# Microcontroller.net
KiCad netlist of a schematic drawn in Altium Designer
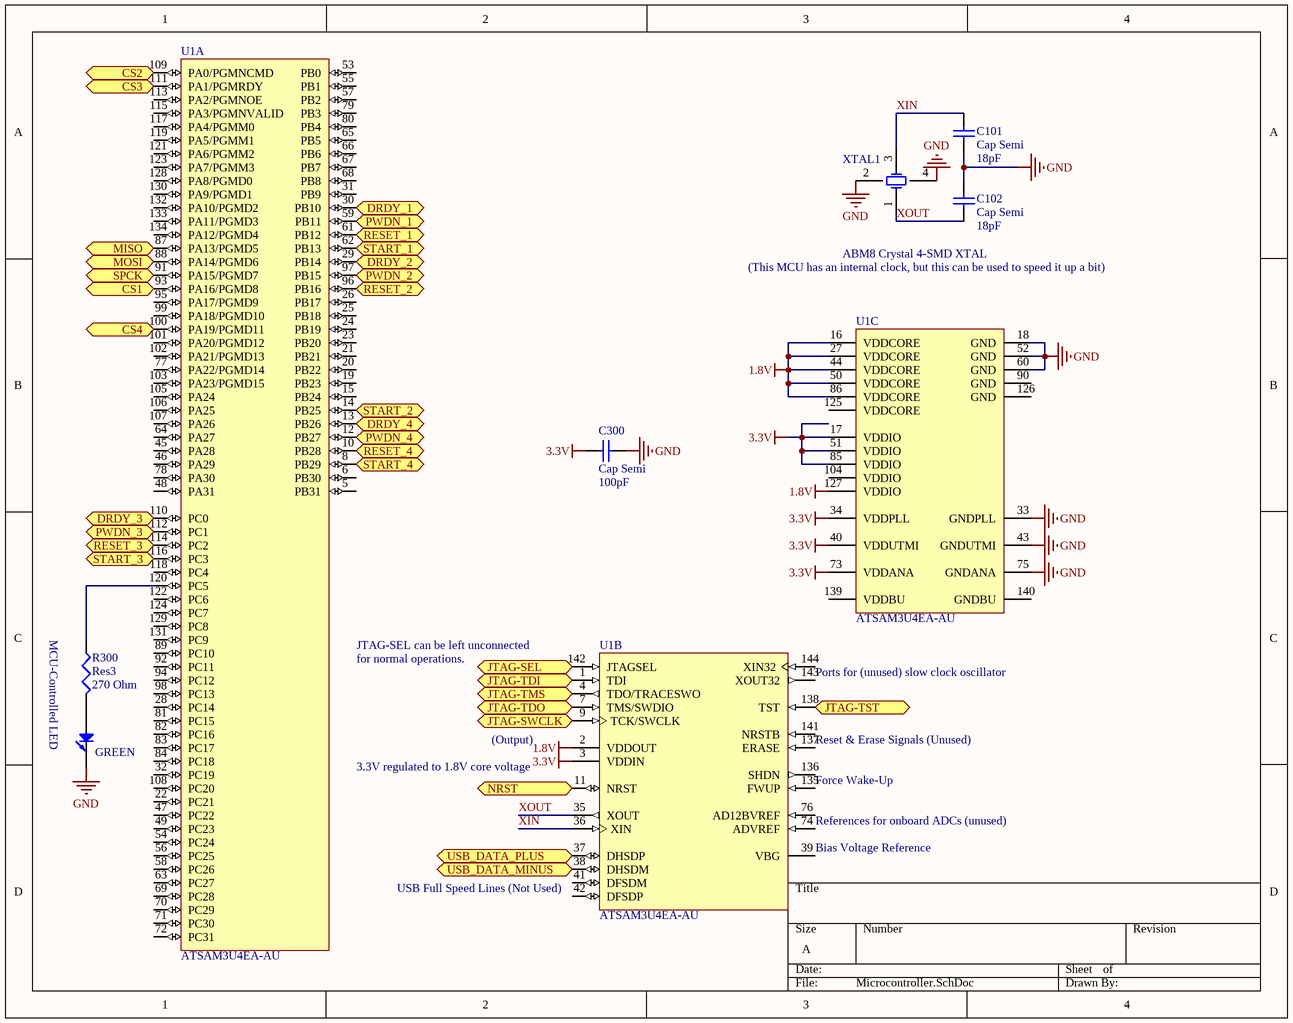
[diagram p0: Microcontroller.SchDoc]

(export (version "E")
  (design (tool "Eeschema 10.0.6"))
  (components
    (comp (ref "C101")
      (value "Cap Semi")
      (footprint "1608[0603]")
      (description "Capacitor (Semiconductor SIM Model)")
      (fields (field (name "ALTIUM_VALUE") "18pF") (field (name "PUBLISHER") "Altium Limited"))
      (libsource (lib "Miscellaneous Devices") (part "Cap Semi"))
    )
    (comp (ref "C102")
      (value "Cap Semi")
      (footprint "1608[0603]")
      (description "Capacitor (Semiconductor SIM Model)")
      (fields (field (name "ALTIUM_VALUE") "18pF") (field (name "PUBLISHER") "Altium Limited"))
      (libsource (lib "Miscellaneous Devices") (part "Cap Semi"))
    )
    (comp (ref "C300")
      (value "Cap Semi")
      (footprint "C1206")
      (description "Capacitor (Semiconductor SIM Model)")
      (fields (field (name "ALTIUM_VALUE") "100pF") (field (name "PUBLISHER") "Altium Limited"))
      (libsource (lib "Miscellaneous Devices") (part "Cap Semi"))
    )
    (comp (ref "LED2")
      (value "GREEN")
      (footprint "1608[0603]")
      (description "led")
      (fields
        (field (name "MANUFACTURER") "Lite-On Inc")
        (field (name "MANUFACTURER PART NUMBER") "LTST-C193KGKT-5A")
      )
      (libsource (lib "common") (part "LED0"))
    )
    (comp (ref "R300")
      (value "Res3")
      (footprint "1608[0603]")
      (description "Resistor")
      (fields (field (name "ALTIUM_VALUE") "270 Ohm") (field (name "PUBLISHER") "Altium Limited"))
      (libsource (lib "Miscellaneous Devices") (part "Res3"))
    )
    (comp (ref "U1")
      (value "ATSAM3U4EA-AU")
      (footprint "144L1_N")
      (fields (field (name "PUBLISHER") "Altium Limited"))
      (libsource (lib "Atmel Microcontroller 32-Bit ARM") (part "ATSAM3U4EA-AU"))
    )
    (comp (ref "XTAL1")
      (value "ABM8 Crystal 4-SMD XTAL")
      (footprint "ABM8 Crystal XTAL")
      (description "SMD Crystal")
      (libsource (lib "common") (part "ABM8 Crystal 4-SMD XTAL_1"))
    )
  )
  (nets
    (net (code "1") (name "/CS1") (class "Default")
      (node (ref "U1") (pin "93") (pinfunction "PA16/PGMD8_93") (pintype "bidirectional"))
    )
    (net (code "2") (name "/CS2") (class "Default")
      (node (ref "U1") (pin "109") (pinfunction "PA0/PGMNCMD_109") (pintype "bidirectional"))
    )
    (net (code "3") (name "/CS3") (class "Default")
      (node (ref "U1") (pin "111") (pinfunction "PA1/PGMRDY_111") (pintype "bidirectional"))
    )
    (net (code "4") (name "/CS4") (class "Default")
      (node (ref "U1") (pin "100") (pinfunction "PA19/PGMD11_100") (pintype "bidirectional"))
    )
    (net (code "5") (name "/DRDY_1") (class "Default")
      (node (ref "U1") (pin "30") (pinfunction "PB10_30") (pintype "bidirectional"))
    )
    (net (code "6") (name "/DRDY_2") (class "Default")
      (node (ref "U1") (pin "29") (pinfunction "PB14_29") (pintype "bidirectional"))
    )
    (net (code "7") (name "/DRDY_3") (class "Default")
      (node (ref "U1") (pin "110") (pinfunction "PC0_110") (pintype "bidirectional"))
    )
    (net (code "8") (name "/DRDY_4") (class "Default")
      (node (ref "U1") (pin "13") (pinfunction "PB26_13") (pintype "bidirectional"))
    )
    (net (code "9") (name "/JTAG-SEL") (class "Default")
      (node (ref "U1") (pin "142") (pinfunction "JTAGSEL_142") (pintype "input"))
    )
    (net (code "10") (name "/JTAG-SWCLK") (class "Default")
      (node (ref "U1") (pin "9") (pinfunction "TCK/SWCLK_9") (pintype "input"))
    )
    (net (code "11") (name "/JTAG-TDI") (class "Default")
      (node (ref "U1") (pin "1") (pinfunction "TDI_1") (pintype "input"))
    )
    (net (code "12") (name "/JTAG-TDO") (class "Default")
      (node (ref "U1") (pin "7") (pinfunction "TMS/SWDIO_7") (pintype "input"))
    )
    (net (code "13") (name "/JTAG-TMS") (class "Default")
      (node (ref "U1") (pin "4") (pinfunction "TDO/TRACESWO_4") (pintype "output"))
    )
    (net (code "14") (name "/JTAG-TST") (class "Default")
      (node (ref "U1") (pin "138") (pinfunction "TST_138") (pintype "input"))
    )
    (net (code "15") (name "/MISO") (class "Default")
      (node (ref "U1") (pin "87") (pinfunction "PA13/PGMD5_87") (pintype "bidirectional"))
    )
    (net (code "16") (name "/MOSI") (class "Default")
      (node (ref "U1") (pin "88") (pinfunction "PA14/PGMD6_88") (pintype "bidirectional"))
    )
    (net (code "17") (name "/NRST") (class "Default")
      (node (ref "U1") (pin "11") (pinfunction "NRST_11") (pintype "bidirectional"))
    )
    (net (code "18") (name "/PWDN_1") (class "Default")
      (node (ref "U1") (pin "59") (pinfunction "PB11_59") (pintype "bidirectional"))
    )
    (net (code "19") (name "/PWDN_2") (class "Default")
      (node (ref "U1") (pin "97") (pinfunction "PB15_97") (pintype "bidirectional"))
    )
    (net (code "20") (name "/PWDN_3") (class "Default")
      (node (ref "U1") (pin "112") (pinfunction "PC1_112") (pintype "bidirectional"))
    )
    (net (code "21") (name "/PWDN_4") (class "Default")
      (node (ref "U1") (pin "12") (pinfunction "PB27_12") (pintype "bidirectional"))
    )
    (net (code "22") (name "/RESET_1") (class "Default")
      (node (ref "U1") (pin "61") (pinfunction "PB12_61") (pintype "bidirectional"))
    )
    (net (code "23") (name "/RESET_2") (class "Default")
      (node (ref "U1") (pin "96") (pinfunction "PB16_96") (pintype "bidirectional"))
    )
    (net (code "24") (name "/RESET_3") (class "Default")
      (node (ref "U1") (pin "114") (pinfunction "PC2_114") (pintype "bidirectional"))
    )
    (net (code "25") (name "/RESET_4") (class "Default")
      (node (ref "U1") (pin "10") (pinfunction "PB28_10") (pintype "bidirectional"))
    )
    (net (code "26") (name "/SPCK") (class "Default")
      (node (ref "U1") (pin "91") (pinfunction "PA15/PGMD7_91") (pintype "bidirectional"))
    )
    (net (code "27") (name "/START_1") (class "Default")
      (node (ref "U1") (pin "62") (pinfunction "PB13_62") (pintype "bidirectional"))
    )
    (net (code "28") (name "/START_2") (class "Default")
      (node (ref "U1") (pin "14") (pinfunction "PB25_14") (pintype "bidirectional"))
    )
    (net (code "29") (name "/START_3") (class "Default")
      (node (ref "U1") (pin "116") (pinfunction "PC3_116") (pintype "bidirectional"))
    )
    (net (code "30") (name "/START_4") (class "Default")
      (node (ref "U1") (pin "8") (pinfunction "PB29_8") (pintype "bidirectional"))
    )
    (net (code "31") (name "/USB_DATA_MINUS") (class "Default")
      (node (ref "U1") (pin "38") (pinfunction "DHSDM_38") (pintype "bidirectional"))
    )
    (net (code "32") (name "/USB_DATA_PLUS") (class "Default")
      (node (ref "U1") (pin "37") (pinfunction "DHSDP_37") (pintype "bidirectional"))
    )
    (net (code "33") (name "/XIN") (class "Default")
      (node (ref "C101") (pin "2") (pinfunction "2_2") (pintype "passive"))
      (node (ref "U1") (pin "36") (pinfunction "XIN_36") (pintype "input"))
      (node (ref "XTAL1") (pin "3") (pinfunction "OSC2_3") (pintype "passive"))
    )
    (net (code "34") (name "/XOUT") (class "Default")
      (node (ref "C102") (pin "1") (pinfunction "1_1") (pintype "passive"))
      (node (ref "U1") (pin "35") (pinfunction "XOUT_35") (pintype "output"))
      (node (ref "XTAL1") (pin "1") (pinfunction "OSC1_1") (pintype "passive"))
    )
    (net (code "35") (name "1.8V") (class "Default")
      (node (ref "U1") (pin "127") (pinfunction "VDDIO_127") (pintype "power_in"))
      (node (ref "U1") (pin "16") (pinfunction "VDDCORE_16") (pintype "power_in"))
      (node (ref "U1") (pin "2") (pinfunction "VDDOUT_2") (pintype "power_in"))
      (node (ref "U1") (pin "27") (pinfunction "VDDCORE_27") (pintype "power_in"))
      (node (ref "U1") (pin "44") (pinfunction "VDDCORE_44") (pintype "power_in"))
      (node (ref "U1") (pin "50") (pinfunction "VDDCORE_50") (pintype "power_in"))
      (node (ref "U1") (pin "86") (pinfunction "VDDCORE_86") (pintype "power_in"))
    )
    (net (code "36") (name "3.3V") (class "Default")
      (node (ref "C300") (pin "1") (pinfunction "1_1") (pintype "passive"))
      (node (ref "U1") (pin "17") (pinfunction "VDDIO_17") (pintype "power_in"))
      (node (ref "U1") (pin "3") (pinfunction "VDDIN_3") (pintype "power_in"))
      (node (ref "U1") (pin "34") (pinfunction "VDDPLL_34") (pintype "power_in"))
      (node (ref "U1") (pin "40") (pinfunction "VDDUTMI_40") (pintype "power_in"))
      (node (ref "U1") (pin "51") (pinfunction "VDDIO_51") (pintype "power_in"))
      (node (ref "U1") (pin "73") (pinfunction "VDDANA_73") (pintype "power_in"))
      (node (ref "U1") (pin "85") (pinfunction "VDDIO_85") (pintype "power_in"))
    )
    (net (code "37") (name "GND") (class "Default")
      (node (ref "C101") (pin "1") (pinfunction "1_1") (pintype "passive"))
      (node (ref "C102") (pin "2") (pinfunction "2_2") (pintype "passive"))
      (node (ref "C300") (pin "2") (pinfunction "2_2") (pintype "passive"))
      (node (ref "LED2") (pin "2") (pinfunction "K_2") (pintype "passive"))
      (node (ref "U1") (pin "18") (pinfunction "GND_18") (pintype "power_in"))
      (node (ref "U1") (pin "33") (pinfunction "GNDPLL_33") (pintype "power_in"))
      (node (ref "U1") (pin "43") (pinfunction "GNDUTMI_43") (pintype "power_in"))
      (node (ref "U1") (pin "52") (pinfunction "GND_52") (pintype "power_in"))
      (node (ref "U1") (pin "60") (pinfunction "GND_60") (pintype "power_in"))
      (node (ref "U1") (pin "75") (pinfunction "GNDANA_75") (pintype "power_in"))
      (node (ref "XTAL1") (pin "2") (pinfunction "GND_2") (pintype "passive"))
      (node (ref "XTAL1") (pin "4") (pinfunction "GND_4") (pintype "power_in"))
    )
    (net (code "38") (name "Net-(LED2-A)") (class "Default")
      (node (ref "LED2") (pin "1") (pinfunction "A_1") (pintype "passive"))
      (node (ref "R300") (pin "2") (pinfunction "2_2") (pintype "passive"))
    )
    (net (code "39") (name "Net-(U1A-PC5)") (class "Default")
      (node (ref "R300") (pin "1") (pinfunction "1_1") (pintype "passive"))
      (node (ref "U1") (pin "120") (pinfunction "PC5_120") (pintype "bidirectional"))
    )
    (net (code "40") (name "unconnected-(U1A-PA2{slash}PGMNOE-Pad113)") (class "Default")
      (node (ref "U1") (pin "113") (pinfunction "PA2/PGMNOE_113") (pintype "bidirectional"))
    )
    (net (code "41") (name "unconnected-(U1A-PA3{slash}PGMNVALID-Pad115)") (class "Default")
      (node (ref "U1") (pin "115") (pinfunction "PA3/PGMNVALID_115") (pintype "bidirectional"))
    )
    (net (code "42") (name "unconnected-(U1A-PA4{slash}PGMM0-Pad117)") (class "Default")
      (node (ref "U1") (pin "117") (pinfunction "PA4/PGMM0_117") (pintype "bidirectional"))
    )
    (net (code "43") (name "unconnected-(U1A-PA5{slash}PGMM1-Pad119)") (class "Default")
      (node (ref "U1") (pin "119") (pinfunction "PA5/PGMM1_119") (pintype "bidirectional"))
    )
    (net (code "44") (name "unconnected-(U1A-PA6{slash}PGMM2-Pad121)") (class "Default")
      (node (ref "U1") (pin "121") (pinfunction "PA6/PGMM2_121") (pintype "bidirectional"))
    )
    (net (code "45") (name "unconnected-(U1A-PA7{slash}PGMM3-Pad123)") (class "Default")
      (node (ref "U1") (pin "123") (pinfunction "PA7/PGMM3_123") (pintype "bidirectional"))
    )
    (net (code "46") (name "unconnected-(U1A-PA8{slash}PGMD0-Pad128)") (class "Default")
      (node (ref "U1") (pin "128") (pinfunction "PA8/PGMD0_128") (pintype "bidirectional"))
    )
    (net (code "47") (name "unconnected-(U1A-PA9{slash}PGMD1-Pad130)") (class "Default")
      (node (ref "U1") (pin "130") (pinfunction "PA9/PGMD1_130") (pintype "bidirectional"))
    )
    (net (code "48") (name "unconnected-(U1A-PA10{slash}PGMD2-Pad132)") (class "Default")
      (node (ref "U1") (pin "132") (pinfunction "PA10/PGMD2_132") (pintype "bidirectional"))
    )
    (net (code "49") (name "unconnected-(U1A-PA11{slash}PGMD3-Pad133)") (class "Default")
      (node (ref "U1") (pin "133") (pinfunction "PA11/PGMD3_133") (pintype "bidirectional"))
    )
    (net (code "50") (name "unconnected-(U1A-PA12{slash}PGMD4-Pad134)") (class "Default")
      (node (ref "U1") (pin "134") (pinfunction "PA12/PGMD4_134") (pintype "bidirectional"))
    )
    (net (code "51") (name "unconnected-(U1A-PA17{slash}PGMD9-Pad95)") (class "Default")
      (node (ref "U1") (pin "95") (pinfunction "PA17/PGMD9_95") (pintype "bidirectional"))
    )
    (net (code "52") (name "unconnected-(U1A-PA18{slash}PGMD10-Pad99)") (class "Default")
      (node (ref "U1") (pin "99") (pinfunction "PA18/PGMD10_99") (pintype "bidirectional"))
    )
    (net (code "53") (name "unconnected-(U1A-PA20{slash}PGMD12-Pad101)") (class "Default")
      (node (ref "U1") (pin "101") (pinfunction "PA20/PGMD12_101") (pintype "bidirectional"))
    )
    (net (code "54") (name "unconnected-(U1A-PA21{slash}PGMD13-Pad102)") (class "Default")
      (node (ref "U1") (pin "102") (pinfunction "PA21/PGMD13_102") (pintype "bidirectional"))
    )
    (net (code "55") (name "unconnected-(U1A-PA22{slash}PGMD14-Pad77)") (class "Default")
      (node (ref "U1") (pin "77") (pinfunction "PA22/PGMD14_77") (pintype "bidirectional"))
    )
    (net (code "56") (name "unconnected-(U1A-PA23{slash}PGMD15-Pad103)") (class "Default")
      (node (ref "U1") (pin "103") (pinfunction "PA23/PGMD15_103") (pintype "bidirectional"))
    )
    (net (code "57") (name "unconnected-(U1A-PA24-Pad105)") (class "Default")
      (node (ref "U1") (pin "105") (pinfunction "PA24_105") (pintype "bidirectional"))
    )
    (net (code "58") (name "unconnected-(U1A-PA25-Pad106)") (class "Default")
      (node (ref "U1") (pin "106") (pinfunction "PA25_106") (pintype "bidirectional"))
    )
    (net (code "59") (name "unconnected-(U1A-PA26-Pad107)") (class "Default")
      (node (ref "U1") (pin "107") (pinfunction "PA26_107") (pintype "bidirectional"))
    )
    (net (code "60") (name "unconnected-(U1A-PA27-Pad64)") (class "Default")
      (node (ref "U1") (pin "64") (pinfunction "PA27_64") (pintype "bidirectional"))
    )
    (net (code "61") (name "unconnected-(U1A-PA28-Pad45)") (class "Default")
      (node (ref "U1") (pin "45") (pinfunction "PA28_45") (pintype "bidirectional"))
    )
    (net (code "62") (name "unconnected-(U1A-PA29-Pad46)") (class "Default")
      (node (ref "U1") (pin "46") (pinfunction "PA29_46") (pintype "bidirectional"))
    )
    (net (code "63") (name "unconnected-(U1A-PA30-Pad78)") (class "Default")
      (node (ref "U1") (pin "78") (pinfunction "PA30_78") (pintype "bidirectional"))
    )
    (net (code "64") (name "unconnected-(U1A-PA31-Pad48)") (class "Default")
      (node (ref "U1") (pin "48") (pinfunction "PA31_48") (pintype "bidirectional"))
    )
    (net (code "65") (name "unconnected-(U1A-PB0-Pad53)") (class "Default")
      (node (ref "U1") (pin "53") (pinfunction "PB0_53") (pintype "bidirectional"))
    )
    (net (code "66") (name "unconnected-(U1A-PB1-Pad55)") (class "Default")
      (node (ref "U1") (pin "55") (pinfunction "PB1_55") (pintype "bidirectional"))
    )
    (net (code "67") (name "unconnected-(U1A-PB2-Pad57)") (class "Default")
      (node (ref "U1") (pin "57") (pinfunction "PB2_57") (pintype "bidirectional"))
    )
    (net (code "68") (name "unconnected-(U1A-PB3-Pad79)") (class "Default")
      (node (ref "U1") (pin "79") (pinfunction "PB3_79") (pintype "bidirectional"))
    )
    (net (code "69") (name "unconnected-(U1A-PB4-Pad80)") (class "Default")
      (node (ref "U1") (pin "80") (pinfunction "PB4_80") (pintype "bidirectional"))
    )
    (net (code "70") (name "unconnected-(U1A-PB5-Pad65)") (class "Default")
      (node (ref "U1") (pin "65") (pinfunction "PB5_65") (pintype "bidirectional"))
    )
    (net (code "71") (name "unconnected-(U1A-PB6-Pad66)") (class "Default")
      (node (ref "U1") (pin "66") (pinfunction "PB6_66") (pintype "bidirectional"))
    )
    (net (code "72") (name "unconnected-(U1A-PB7-Pad67)") (class "Default")
      (node (ref "U1") (pin "67") (pinfunction "PB7_67") (pintype "bidirectional"))
    )
    (net (code "73") (name "unconnected-(U1A-PB8-Pad68)") (class "Default")
      (node (ref "U1") (pin "68") (pinfunction "PB8_68") (pintype "bidirectional"))
    )
    (net (code "74") (name "unconnected-(U1A-PB9-Pad31)") (class "Default")
      (node (ref "U1") (pin "31") (pinfunction "PB9_31") (pintype "bidirectional"))
    )
    (net (code "75") (name "unconnected-(U1A-PB17-Pad26)") (class "Default")
      (node (ref "U1") (pin "26") (pinfunction "PB17_26") (pintype "bidirectional"))
    )
    (net (code "76") (name "unconnected-(U1A-PB18-Pad25)") (class "Default")
      (node (ref "U1") (pin "25") (pinfunction "PB18_25") (pintype "bidirectional"))
    )
    (net (code "77") (name "unconnected-(U1A-PB19-Pad24)") (class "Default")
      (node (ref "U1") (pin "24") (pinfunction "PB19_24") (pintype "bidirectional"))
    )
    (net (code "78") (name "unconnected-(U1A-PB20-Pad23)") (class "Default")
      (node (ref "U1") (pin "23") (pinfunction "PB20_23") (pintype "bidirectional"))
    )
    (net (code "79") (name "unconnected-(U1A-PB21-Pad21)") (class "Default")
      (node (ref "U1") (pin "21") (pinfunction "PB21_21") (pintype "bidirectional"))
    )
    (net (code "80") (name "unconnected-(U1A-PB22-Pad20)") (class "Default")
      (node (ref "U1") (pin "20") (pinfunction "PB22_20") (pintype "bidirectional"))
    )
    (net (code "81") (name "unconnected-(U1A-PB23-Pad19)") (class "Default")
      (node (ref "U1") (pin "19") (pinfunction "PB23_19") (pintype "bidirectional"))
    )
    (net (code "82") (name "unconnected-(U1A-PB24-Pad15)") (class "Default")
      (node (ref "U1") (pin "15") (pinfunction "PB24_15") (pintype "bidirectional"))
    )
    (net (code "83") (name "unconnected-(U1A-PB30-Pad6)") (class "Default")
      (node (ref "U1") (pin "6") (pinfunction "PB30_6") (pintype "bidirectional"))
    )
    (net (code "84") (name "unconnected-(U1A-PB31-Pad5)") (class "Default")
      (node (ref "U1") (pin "5") (pinfunction "PB31_5") (pintype "bidirectional"))
    )
    (net (code "85") (name "unconnected-(U1A-PC4-Pad118)") (class "Default")
      (node (ref "U1") (pin "118") (pinfunction "PC4_118") (pintype "bidirectional"))
    )
    (net (code "86") (name "unconnected-(U1A-PC6-Pad122)") (class "Default")
      (node (ref "U1") (pin "122") (pinfunction "PC6_122") (pintype "bidirectional"))
    )
    (net (code "87") (name "unconnected-(U1A-PC7-Pad124)") (class "Default")
      (node (ref "U1") (pin "124") (pinfunction "PC7_124") (pintype "bidirectional"))
    )
    (net (code "88") (name "unconnected-(U1A-PC8-Pad129)") (class "Default")
      (node (ref "U1") (pin "129") (pinfunction "PC8_129") (pintype "bidirectional"))
    )
    (net (code "89") (name "unconnected-(U1A-PC9-Pad131)") (class "Default")
      (node (ref "U1") (pin "131") (pinfunction "PC9_131") (pintype "bidirectional"))
    )
    (net (code "90") (name "unconnected-(U1A-PC10-Pad89)") (class "Default")
      (node (ref "U1") (pin "89") (pinfunction "PC10_89") (pintype "bidirectional"))
    )
    (net (code "91") (name "unconnected-(U1A-PC11-Pad92)") (class "Default")
      (node (ref "U1") (pin "92") (pinfunction "PC11_92") (pintype "bidirectional"))
    )
    (net (code "92") (name "unconnected-(U1A-PC12-Pad94)") (class "Default")
      (node (ref "U1") (pin "94") (pinfunction "PC12_94") (pintype "bidirectional"))
    )
    (net (code "93") (name "unconnected-(U1A-PC13-Pad98)") (class "Default")
      (node (ref "U1") (pin "98") (pinfunction "PC13_98") (pintype "bidirectional"))
    )
    (net (code "94") (name "unconnected-(U1A-PC14-Pad28)") (class "Default")
      (node (ref "U1") (pin "28") (pinfunction "PC14_28") (pintype "bidirectional"))
    )
    (net (code "95") (name "unconnected-(U1A-PC15-Pad81)") (class "Default")
      (node (ref "U1") (pin "81") (pinfunction "PC15_81") (pintype "bidirectional"))
    )
    (net (code "96") (name "unconnected-(U1A-PC16-Pad82)") (class "Default")
      (node (ref "U1") (pin "82") (pinfunction "PC16_82") (pintype "bidirectional"))
    )
    (net (code "97") (name "unconnected-(U1A-PC17-Pad83)") (class "Default")
      (node (ref "U1") (pin "83") (pinfunction "PC17_83") (pintype "bidirectional"))
    )
    (net (code "98") (name "unconnected-(U1A-PC18-Pad84)") (class "Default")
      (node (ref "U1") (pin "84") (pinfunction "PC18_84") (pintype "bidirectional"))
    )
    (net (code "99") (name "unconnected-(U1A-PC19-Pad32)") (class "Default")
      (node (ref "U1") (pin "32") (pinfunction "PC19_32") (pintype "bidirectional"))
    )
    (net (code "100") (name "unconnected-(U1A-PC20-Pad108)") (class "Default")
      (node (ref "U1") (pin "108") (pinfunction "PC20_108") (pintype "bidirectional"))
    )
    (net (code "101") (name "unconnected-(U1A-PC21-Pad22)") (class "Default")
      (node (ref "U1") (pin "22") (pinfunction "PC21_22") (pintype "bidirectional"))
    )
    (net (code "102") (name "unconnected-(U1A-PC22-Pad47)") (class "Default")
      (node (ref "U1") (pin "47") (pinfunction "PC22_47") (pintype "bidirectional"))
    )
    (net (code "103") (name "unconnected-(U1A-PC23-Pad49)") (class "Default")
      (node (ref "U1") (pin "49") (pinfunction "PC23_49") (pintype "bidirectional"))
    )
    (net (code "104") (name "unconnected-(U1A-PC24-Pad54)") (class "Default")
      (node (ref "U1") (pin "54") (pinfunction "PC24_54") (pintype "bidirectional"))
    )
    (net (code "105") (name "unconnected-(U1A-PC25-Pad56)") (class "Default")
      (node (ref "U1") (pin "56") (pinfunction "PC25_56") (pintype "bidirectional"))
    )
    (net (code "106") (name "unconnected-(U1A-PC26-Pad58)") (class "Default")
      (node (ref "U1") (pin "58") (pinfunction "PC26_58") (pintype "bidirectional"))
    )
    (net (code "107") (name "unconnected-(U1A-PC27-Pad63)") (class "Default")
      (node (ref "U1") (pin "63") (pinfunction "PC27_63") (pintype "bidirectional"))
    )
    (net (code "108") (name "unconnected-(U1A-PC28-Pad69)") (class "Default")
      (node (ref "U1") (pin "69") (pinfunction "PC28_69") (pintype "bidirectional"))
    )
    (net (code "109") (name "unconnected-(U1A-PC29-Pad70)") (class "Default")
      (node (ref "U1") (pin "70") (pinfunction "PC29_70") (pintype "bidirectional"))
    )
    (net (code "110") (name "unconnected-(U1A-PC30-Pad71)") (class "Default")
      (node (ref "U1") (pin "71") (pinfunction "PC30_71") (pintype "bidirectional"))
    )
    (net (code "111") (name "unconnected-(U1A-PC31-Pad72)") (class "Default")
      (node (ref "U1") (pin "72") (pinfunction "PC31_72") (pintype "bidirectional"))
    )
    (net (code "112") (name "unconnected-(U1B-AD12BVREF-Pad76)") (class "Default")
      (node (ref "U1") (pin "76") (pinfunction "AD12BVREF_76") (pintype "input"))
    )
    (net (code "113") (name "unconnected-(U1B-ADVREF-Pad74)") (class "Default")
      (node (ref "U1") (pin "74") (pinfunction "ADVREF_74") (pintype "input"))
    )
    (net (code "114") (name "unconnected-(U1B-DFSDM-Pad41)") (class "Default")
      (node (ref "U1") (pin "41") (pinfunction "DFSDM_41") (pintype "bidirectional"))
    )
    (net (code "115") (name "unconnected-(U1B-DFSDP-Pad42)") (class "Default")
      (node (ref "U1") (pin "42") (pinfunction "DFSDP_42") (pintype "bidirectional"))
    )
    (net (code "116") (name "unconnected-(U1B-ERASE-Pad137)") (class "Default")
      (node (ref "U1") (pin "137") (pinfunction "ERASE_137") (pintype "input"))
    )
    (net (code "117") (name "unconnected-(U1B-FWUP-Pad135)") (class "Default")
      (node (ref "U1") (pin "135") (pinfunction "FWUP_135") (pintype "input"))
    )
    (net (code "118") (name "unconnected-(U1B-NRSTB-Pad141)") (class "Default")
      (node (ref "U1") (pin "141") (pinfunction "NRSTB_141") (pintype "input"))
    )
    (net (code "119") (name "unconnected-(U1B-SHDN-Pad136)") (class "Default")
      (node (ref "U1") (pin "136") (pinfunction "SHDN_136") (pintype "output"))
    )
    (net (code "120") (name "unconnected-(U1B-VBG-Pad39)") (class "Default")
      (node (ref "U1") (pin "39") (pinfunction "VBG_39") (pintype "passive"))
    )
    (net (code "121") (name "unconnected-(U1B-XIN32-Pad144)") (class "Default")
      (node (ref "U1") (pin "144") (pinfunction "XIN32_144") (pintype "input"))
    )
    (net (code "122") (name "unconnected-(U1B-XOUT32-Pad143)") (class "Default")
      (node (ref "U1") (pin "143") (pinfunction "XOUT32_143") (pintype "output"))
    )
    (net (code "123") (name "unconnected-(U1C-GND-Pad90)") (class "Default")
      (node (ref "U1") (pin "90") (pinfunction "GND_90") (pintype "power_in"))
    )
    (net (code "124") (name "unconnected-(U1C-GND-Pad126)") (class "Default")
      (node (ref "U1") (pin "126") (pinfunction "GND_126") (pintype "power_in"))
    )
    (net (code "125") (name "unconnected-(U1C-GNDBU-Pad140)") (class "Default")
      (node (ref "U1") (pin "140") (pinfunction "GNDBU_140") (pintype "power_in"))
    )
    (net (code "126") (name "unconnected-(U1C-VDDBU-Pad139)") (class "Default")
      (node (ref "U1") (pin "139") (pinfunction "VDDBU_139") (pintype "power_in"))
    )
    (net (code "127") (name "unconnected-(U1C-VDDCORE-Pad125)") (class "Default")
      (node (ref "U1") (pin "125") (pinfunction "VDDCORE_125") (pintype "power_in"))
    )
    (net (code "128") (name "unconnected-(U1C-VDDIO-Pad104)") (class "Default")
      (node (ref "U1") (pin "104") (pinfunction "VDDIO_104") (pintype "power_in"))
    )
  )
)
